# 09_FPGA_E.net
KiCad netlist of a schematic drawn in Altium Designer
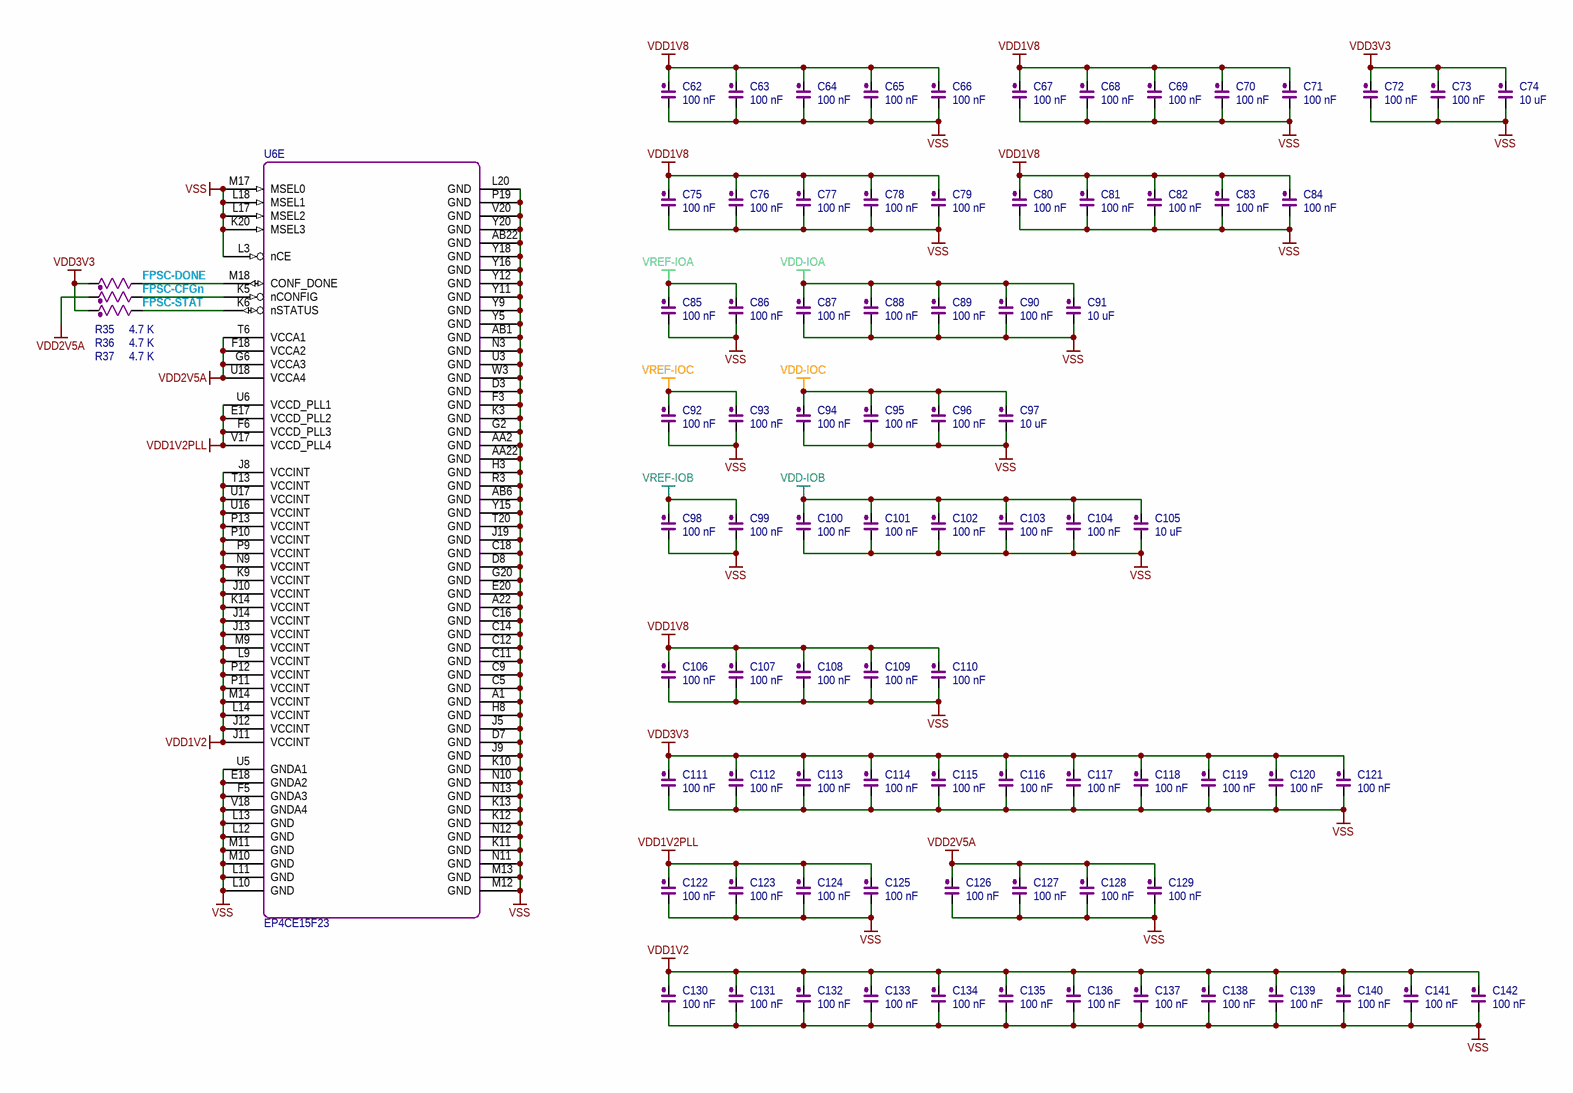
[diagram p0: 09_FPGA_E.SchDoc]

(export (version "E")
  (design (tool "Eeschema 10.0.6"))
  (components
    (comp (ref "C62")
      (value "100 nF")
      (footprint "0402A1")
      (description "Normal Capacitor")
      (fields
        (field (name "PARTNUMBER") "0")
        (field (name "PUBLISHER") "Cowin")
        (field (name "DESIGNER") "shyul")
      )
      (libsource (lib "Basc_1_Passive") (part "CAP"))
    )
    (comp (ref "C63")
      (value "100 nF")
      (footprint "0402A1")
      (description "Normal Capacitor")
      (fields
        (field (name "PARTNUMBER") "0")
        (field (name "PUBLISHER") "Cowin")
        (field (name "DESIGNER") "shyul")
      )
      (libsource (lib "Basc_1_Passive") (part "CAP"))
    )
    (comp (ref "C64")
      (value "100 nF")
      (footprint "0402A1")
      (description "Normal Capacitor")
      (fields
        (field (name "PARTNUMBER") "0")
        (field (name "PUBLISHER") "Cowin")
        (field (name "DESIGNER") "shyul")
      )
      (libsource (lib "Basc_1_Passive") (part "CAP"))
    )
    (comp (ref "C65")
      (value "100 nF")
      (footprint "0402A1")
      (description "Normal Capacitor")
      (fields
        (field (name "PARTNUMBER") "0")
        (field (name "PUBLISHER") "Cowin")
        (field (name "DESIGNER") "shyul")
      )
      (libsource (lib "Basc_1_Passive") (part "CAP"))
    )
    (comp (ref "C66")
      (value "100 nF")
      (footprint "0402A1")
      (description "Normal Capacitor")
      (fields
        (field (name "PARTNUMBER") "0")
        (field (name "PUBLISHER") "Cowin")
        (field (name "DESIGNER") "shyul")
      )
      (libsource (lib "Basc_1_Passive") (part "CAP"))
    )
    (comp (ref "C67")
      (value "100 nF")
      (footprint "0402A1")
      (description "Normal Capacitor")
      (fields
        (field (name "PARTNUMBER") "0")
        (field (name "PUBLISHER") "Cowin")
        (field (name "DESIGNER") "shyul")
      )
      (libsource (lib "Basc_1_Passive") (part "CAP"))
    )
    (comp (ref "C68")
      (value "100 nF")
      (footprint "0402A1")
      (description "Normal Capacitor")
      (fields
        (field (name "PARTNUMBER") "0")
        (field (name "PUBLISHER") "Cowin")
        (field (name "DESIGNER") "shyul")
      )
      (libsource (lib "Basc_1_Passive") (part "CAP"))
    )
    (comp (ref "C69")
      (value "100 nF")
      (footprint "0402A1")
      (description "Normal Capacitor")
      (fields
        (field (name "PARTNUMBER") "0")
        (field (name "PUBLISHER") "Cowin")
        (field (name "DESIGNER") "shyul")
      )
      (libsource (lib "Basc_1_Passive") (part "CAP"))
    )
    (comp (ref "C70")
      (value "100 nF")
      (footprint "0402A1")
      (description "Normal Capacitor")
      (fields
        (field (name "PARTNUMBER") "0")
        (field (name "PUBLISHER") "Cowin")
        (field (name "DESIGNER") "shyul")
      )
      (libsource (lib "Basc_1_Passive") (part "CAP"))
    )
    (comp (ref "C71")
      (value "100 nF")
      (footprint "0402A1")
      (description "Normal Capacitor")
      (fields
        (field (name "PARTNUMBER") "0")
        (field (name "PUBLISHER") "Cowin")
        (field (name "DESIGNER") "shyul")
      )
      (libsource (lib "Basc_1_Passive") (part "CAP"))
    )
    (comp (ref "C72")
      (value "100 nF")
      (footprint "0402A1")
      (description "Normal Capacitor")
      (fields
        (field (name "PARTNUMBER") "0")
        (field (name "PUBLISHER") "Cowin")
        (field (name "DESIGNER") "shyul")
      )
      (libsource (lib "Basc_1_Passive") (part "CAP"))
    )
    (comp (ref "C73")
      (value "100 nF")
      (footprint "0402A1")
      (description "Normal Capacitor")
      (fields
        (field (name "PARTNUMBER") "0")
        (field (name "PUBLISHER") "Cowin")
        (field (name "DESIGNER") "shyul")
      )
      (libsource (lib "Basc_1_Passive") (part "CAP"))
    )
    (comp (ref "C74")
      (value "10 uF")
      (footprint "0603A1")
      (description "Normal Capacitor")
      (fields
        (field (name "PARTNUMBER") "0")
        (field (name "PUBLISHER") "Cowin")
        (field (name "DESIGNER") "shyul")
      )
      (libsource (lib "Basc_1_Passive") (part "CAP"))
    )
    (comp (ref "C75")
      (value "100 nF")
      (footprint "0402A1")
      (description "Normal Capacitor")
      (fields
        (field (name "PARTNUMBER") "0")
        (field (name "PUBLISHER") "Cowin")
        (field (name "DESIGNER") "shyul")
      )
      (libsource (lib "Basc_1_Passive") (part "CAP"))
    )
    (comp (ref "C76")
      (value "100 nF")
      (footprint "0402A1")
      (description "Normal Capacitor")
      (fields
        (field (name "PARTNUMBER") "0")
        (field (name "PUBLISHER") "Cowin")
        (field (name "DESIGNER") "shyul")
      )
      (libsource (lib "Basc_1_Passive") (part "CAP"))
    )
    (comp (ref "C77")
      (value "100 nF")
      (footprint "0402A1")
      (description "Normal Capacitor")
      (fields
        (field (name "PARTNUMBER") "0")
        (field (name "PUBLISHER") "Cowin")
        (field (name "DESIGNER") "shyul")
      )
      (libsource (lib "Basc_1_Passive") (part "CAP"))
    )
    (comp (ref "C78")
      (value "100 nF")
      (footprint "0402A1")
      (description "Normal Capacitor")
      (fields
        (field (name "PARTNUMBER") "0")
        (field (name "PUBLISHER") "Cowin")
        (field (name "DESIGNER") "shyul")
      )
      (libsource (lib "Basc_1_Passive") (part "CAP"))
    )
    (comp (ref "C79")
      (value "100 nF")
      (footprint "0402A1")
      (description "Normal Capacitor")
      (fields
        (field (name "PARTNUMBER") "0")
        (field (name "PUBLISHER") "Cowin")
        (field (name "DESIGNER") "shyul")
      )
      (libsource (lib "Basc_1_Passive") (part "CAP"))
    )
    (comp (ref "C80")
      (value "100 nF")
      (footprint "0402A1")
      (description "Normal Capacitor")
      (fields
        (field (name "PARTNUMBER") "0")
        (field (name "PUBLISHER") "Cowin")
        (field (name "DESIGNER") "shyul")
      )
      (libsource (lib "Basc_1_Passive") (part "CAP"))
    )
    (comp (ref "C81")
      (value "100 nF")
      (footprint "0402A1")
      (description "Normal Capacitor")
      (fields
        (field (name "PARTNUMBER") "0")
        (field (name "PUBLISHER") "Cowin")
        (field (name "DESIGNER") "shyul")
      )
      (libsource (lib "Basc_1_Passive") (part "CAP"))
    )
    (comp (ref "C82")
      (value "100 nF")
      (footprint "0402A1")
      (description "Normal Capacitor")
      (fields
        (field (name "PARTNUMBER") "0")
        (field (name "PUBLISHER") "Cowin")
        (field (name "DESIGNER") "shyul")
      )
      (libsource (lib "Basc_1_Passive") (part "CAP"))
    )
    (comp (ref "C83")
      (value "100 nF")
      (footprint "0402A1")
      (description "Normal Capacitor")
      (fields
        (field (name "PARTNUMBER") "0")
        (field (name "PUBLISHER") "Cowin")
        (field (name "DESIGNER") "shyul")
      )
      (libsource (lib "Basc_1_Passive") (part "CAP"))
    )
    (comp (ref "C84")
      (value "100 nF")
      (footprint "0402A1")
      (description "Normal Capacitor")
      (fields
        (field (name "PARTNUMBER") "0")
        (field (name "PUBLISHER") "Cowin")
        (field (name "DESIGNER") "shyul")
      )
      (libsource (lib "Basc_1_Passive") (part "CAP"))
    )
    (comp (ref "C85")
      (value "100 nF")
      (footprint "0402A1")
      (description "Normal Capacitor")
      (fields
        (field (name "PARTNUMBER") "0")
        (field (name "PUBLISHER") "Cowin")
        (field (name "DESIGNER") "shyul")
      )
      (libsource (lib "Basc_1_Passive") (part "CAP"))
    )
    (comp (ref "C86")
      (value "100 nF")
      (footprint "0402A1")
      (description "Normal Capacitor")
      (fields
        (field (name "PARTNUMBER") "0")
        (field (name "PUBLISHER") "Cowin")
        (field (name "DESIGNER") "shyul")
      )
      (libsource (lib "Basc_1_Passive") (part "CAP"))
    )
    (comp (ref "C87")
      (value "100 nF")
      (footprint "0402A1")
      (description "Normal Capacitor")
      (fields
        (field (name "PARTNUMBER") "0")
        (field (name "PUBLISHER") "Cowin")
        (field (name "DESIGNER") "shyul")
      )
      (libsource (lib "Basc_1_Passive") (part "CAP"))
    )
    (comp (ref "C88")
      (value "100 nF")
      (footprint "0402A1")
      (description "Normal Capacitor")
      (fields
        (field (name "PARTNUMBER") "0")
        (field (name "PUBLISHER") "Cowin")
        (field (name "DESIGNER") "shyul")
      )
      (libsource (lib "Basc_1_Passive") (part "CAP"))
    )
    (comp (ref "C89")
      (value "100 nF")
      (footprint "0402A1")
      (description "Normal Capacitor")
      (fields
        (field (name "PARTNUMBER") "0")
        (field (name "PUBLISHER") "Cowin")
        (field (name "DESIGNER") "shyul")
      )
      (libsource (lib "Basc_1_Passive") (part "CAP"))
    )
    (comp (ref "C90")
      (value "100 nF")
      (footprint "0402A1")
      (description "Normal Capacitor")
      (fields
        (field (name "PARTNUMBER") "0")
        (field (name "PUBLISHER") "Cowin")
        (field (name "DESIGNER") "shyul")
      )
      (libsource (lib "Basc_1_Passive") (part "CAP"))
    )
    (comp (ref "C91")
      (value "10 uF")
      (footprint "0603A1")
      (description "Normal Capacitor")
      (fields
        (field (name "PARTNUMBER") "0")
        (field (name "PUBLISHER") "Cowin")
        (field (name "DESIGNER") "shyul")
      )
      (libsource (lib "Basc_1_Passive") (part "CAP"))
    )
    (comp (ref "C92")
      (value "100 nF")
      (footprint "0402A1")
      (description "Normal Capacitor")
      (fields
        (field (name "PARTNUMBER") "0")
        (field (name "PUBLISHER") "Cowin")
        (field (name "DESIGNER") "shyul")
      )
      (libsource (lib "Basc_1_Passive") (part "CAP"))
    )
    (comp (ref "C93")
      (value "100 nF")
      (footprint "0402A1")
      (description "Normal Capacitor")
      (fields
        (field (name "PARTNUMBER") "0")
        (field (name "PUBLISHER") "Cowin")
        (field (name "DESIGNER") "shyul")
      )
      (libsource (lib "Basc_1_Passive") (part "CAP"))
    )
    (comp (ref "C94")
      (value "100 nF")
      (footprint "0402A1")
      (description "Normal Capacitor")
      (fields
        (field (name "PARTNUMBER") "0")
        (field (name "PUBLISHER") "Cowin")
        (field (name "DESIGNER") "shyul")
      )
      (libsource (lib "Basc_1_Passive") (part "CAP"))
    )
    (comp (ref "C95")
      (value "100 nF")
      (footprint "0402A1")
      (description "Normal Capacitor")
      (fields
        (field (name "PARTNUMBER") "0")
        (field (name "PUBLISHER") "Cowin")
        (field (name "DESIGNER") "shyul")
      )
      (libsource (lib "Basc_1_Passive") (part "CAP"))
    )
    (comp (ref "C96")
      (value "100 nF")
      (footprint "0402A1")
      (description "Normal Capacitor")
      (fields
        (field (name "PARTNUMBER") "0")
        (field (name "PUBLISHER") "Cowin")
        (field (name "DESIGNER") "shyul")
      )
      (libsource (lib "Basc_1_Passive") (part "CAP"))
    )
    (comp (ref "C97")
      (value "10 uF")
      (footprint "0603A1")
      (description "Normal Capacitor")
      (fields
        (field (name "PARTNUMBER") "0")
        (field (name "PUBLISHER") "Cowin")
        (field (name "DESIGNER") "shyul")
      )
      (libsource (lib "Basc_1_Passive") (part "CAP"))
    )
    (comp (ref "C98")
      (value "100 nF")
      (footprint "0402A1")
      (description "Normal Capacitor")
      (fields
        (field (name "PARTNUMBER") "0")
        (field (name "PUBLISHER") "Cowin")
        (field (name "DESIGNER") "shyul")
      )
      (libsource (lib "Basc_1_Passive") (part "CAP"))
    )
    (comp (ref "C99")
      (value "100 nF")
      (footprint "0402A1")
      (description "Normal Capacitor")
      (fields
        (field (name "PARTNUMBER") "0")
        (field (name "PUBLISHER") "Cowin")
        (field (name "DESIGNER") "shyul")
      )
      (libsource (lib "Basc_1_Passive") (part "CAP"))
    )
    (comp (ref "C100")
      (value "100 nF")
      (footprint "0402A1")
      (description "Normal Capacitor")
      (fields
        (field (name "PARTNUMBER") "0")
        (field (name "PUBLISHER") "Cowin")
        (field (name "DESIGNER") "shyul")
      )
      (libsource (lib "Basc_1_Passive") (part "CAP"))
    )
    (comp (ref "C101")
      (value "100 nF")
      (footprint "0402A1")
      (description "Normal Capacitor")
      (fields
        (field (name "PARTNUMBER") "0")
        (field (name "PUBLISHER") "Cowin")
        (field (name "DESIGNER") "shyul")
      )
      (libsource (lib "Basc_1_Passive") (part "CAP"))
    )
    (comp (ref "C102")
      (value "100 nF")
      (footprint "0402A1")
      (description "Normal Capacitor")
      (fields
        (field (name "PARTNUMBER") "0")
        (field (name "PUBLISHER") "Cowin")
        (field (name "DESIGNER") "shyul")
      )
      (libsource (lib "Basc_1_Passive") (part "CAP"))
    )
    (comp (ref "C103")
      (value "100 nF")
      (footprint "0402BG")
      (description "Normal Capacitor")
      (fields
        (field (name "PARTNUMBER") "0")
        (field (name "PUBLISHER") "Cowin")
        (field (name "DESIGNER") "shyul")
      )
      (libsource (lib "Basc_1_Passive") (part "CAP"))
    )
    (comp (ref "C104")
      (value "100 nF")
      (footprint "0402BG")
      (description "Normal Capacitor")
      (fields
        (field (name "PARTNUMBER") "0")
        (field (name "PUBLISHER") "Cowin")
        (field (name "DESIGNER") "shyul")
      )
      (libsource (lib "Basc_1_Passive") (part "CAP"))
    )
    (comp (ref "C105")
      (value "10 uF")
      (footprint "0603A1")
      (description "Normal Capacitor")
      (fields
        (field (name "PARTNUMBER") "0")
        (field (name "PUBLISHER") "Cowin")
        (field (name "DESIGNER") "shyul")
      )
      (libsource (lib "Basc_1_Passive") (part "CAP"))
    )
    (comp (ref "C106")
      (value "100 nF")
      (footprint "0402BG")
      (description "Normal Capacitor")
      (fields
        (field (name "PARTNUMBER") "0")
        (field (name "PUBLISHER") "Cowin")
        (field (name "DESIGNER") "shyul")
      )
      (libsource (lib "Basc_1_Passive") (part "CAP"))
    )
    (comp (ref "C107")
      (value "100 nF")
      (footprint "0402BG")
      (description "Normal Capacitor")
      (fields
        (field (name "PARTNUMBER") "0")
        (field (name "PUBLISHER") "Cowin")
        (field (name "DESIGNER") "shyul")
      )
      (libsource (lib "Basc_1_Passive") (part "CAP"))
    )
    (comp (ref "C108")
      (value "100 nF")
      (footprint "0402BG")
      (description "Normal Capacitor")
      (fields
        (field (name "PARTNUMBER") "0")
        (field (name "PUBLISHER") "Cowin")
        (field (name "DESIGNER") "shyul")
      )
      (libsource (lib "Basc_1_Passive") (part "CAP"))
    )
    (comp (ref "C109")
      (value "100 nF")
      (footprint "0402BG")
      (description "Normal Capacitor")
      (fields
        (field (name "PARTNUMBER") "0")
        (field (name "PUBLISHER") "Cowin")
        (field (name "DESIGNER") "shyul")
      )
      (libsource (lib "Basc_1_Passive") (part "CAP"))
    )
    (comp (ref "C110")
      (value "100 nF")
      (footprint "0402BG")
      (description "Normal Capacitor")
      (fields
        (field (name "PARTNUMBER") "0")
        (field (name "PUBLISHER") "Cowin")
        (field (name "DESIGNER") "shyul")
      )
      (libsource (lib "Basc_1_Passive") (part "CAP"))
    )
    (comp (ref "C111")
      (value "100 nF")
      (footprint "0402BG")
      (description "Normal Capacitor")
      (fields
        (field (name "PARTNUMBER") "0")
        (field (name "PUBLISHER") "Cowin")
        (field (name "DESIGNER") "shyul")
      )
      (libsource (lib "Basc_1_Passive") (part "CAP"))
    )
    (comp (ref "C112")
      (value "100 nF")
      (footprint "0402BG")
      (description "Normal Capacitor")
      (fields
        (field (name "PARTNUMBER") "0")
        (field (name "PUBLISHER") "Cowin")
        (field (name "DESIGNER") "shyul")
      )
      (libsource (lib "Basc_1_Passive") (part "CAP"))
    )
    (comp (ref "C113")
      (value "100 nF")
      (footprint "0402BG")
      (description "Normal Capacitor")
      (fields
        (field (name "PARTNUMBER") "0")
        (field (name "PUBLISHER") "Cowin")
        (field (name "DESIGNER") "shyul")
      )
      (libsource (lib "Basc_1_Passive") (part "CAP"))
    )
    (comp (ref "C114")
      (value "100 nF")
      (footprint "0402BG")
      (description "Normal Capacitor")
      (fields
        (field (name "PARTNUMBER") "0")
        (field (name "PUBLISHER") "Cowin")
        (field (name "DESIGNER") "shyul")
      )
      (libsource (lib "Basc_1_Passive") (part "CAP"))
    )
    (comp (ref "C115")
      (value "100 nF")
      (footprint "0402BG")
      (description "Normal Capacitor")
      (fields
        (field (name "PARTNUMBER") "0")
        (field (name "PUBLISHER") "Cowin")
        (field (name "DESIGNER") "shyul")
      )
      (libsource (lib "Basc_1_Passive") (part "CAP"))
    )
    (comp (ref "C116")
      (value "100 nF")
      (footprint "0402BG")
      (description "Normal Capacitor")
      (fields
        (field (name "PARTNUMBER") "0")
        (field (name "PUBLISHER") "Cowin")
        (field (name "DESIGNER") "shyul")
      )
      (libsource (lib "Basc_1_Passive") (part "CAP"))
    )
    (comp (ref "C117")
      (value "100 nF")
      (footprint "0402BG")
      (description "Normal Capacitor")
      (fields
        (field (name "PARTNUMBER") "0")
        (field (name "PUBLISHER") "Cowin")
        (field (name "DESIGNER") "shyul")
      )
      (libsource (lib "Basc_1_Passive") (part "CAP"))
    )
    (comp (ref "C118")
      (value "100 nF")
      (footprint "0402BG")
      (description "Normal Capacitor")
      (fields
        (field (name "PARTNUMBER") "0")
        (field (name "PUBLISHER") "Cowin")
        (field (name "DESIGNER") "shyul")
      )
      (libsource (lib "Basc_1_Passive") (part "CAP"))
    )
    (comp (ref "C119")
      (value "100 nF")
      (footprint "0402BG")
      (description "Normal Capacitor")
      (fields
        (field (name "PARTNUMBER") "0")
        (field (name "PUBLISHER") "Cowin")
        (field (name "DESIGNER") "shyul")
      )
      (libsource (lib "Basc_1_Passive") (part "CAP"))
    )
    (comp (ref "C120")
      (value "100 nF")
      (footprint "0402BG")
      (description "Normal Capacitor")
      (fields
        (field (name "PARTNUMBER") "0")
        (field (name "PUBLISHER") "Cowin")
        (field (name "DESIGNER") "shyul")
      )
      (libsource (lib "Basc_1_Passive") (part "CAP"))
    )
    (comp (ref "C121")
      (value "100 nF")
      (footprint "0402BG")
      (description "Normal Capacitor")
      (fields
        (field (name "PARTNUMBER") "0")
        (field (name "PUBLISHER") "Cowin")
        (field (name "DESIGNER") "shyul")
      )
      (libsource (lib "Basc_1_Passive") (part "CAP"))
    )
    (comp (ref "C122")
      (value "100 nF")
      (footprint "0402BG")
      (description "Normal Capacitor")
      (fields
        (field (name "PARTNUMBER") "0")
        (field (name "PUBLISHER") "Cowin")
        (field (name "DESIGNER") "shyul")
      )
      (libsource (lib "Basc_1_Passive") (part "CAP"))
    )
    (comp (ref "C123")
      (value "100 nF")
      (footprint "0402BG")
      (description "Normal Capacitor")
      (fields
        (field (name "PARTNUMBER") "0")
        (field (name "PUBLISHER") "Cowin")
        (field (name "DESIGNER") "shyul")
      )
      (libsource (lib "Basc_1_Passive") (part "CAP"))
    )
    (comp (ref "C124")
      (value "100 nF")
      (footprint "0402BG")
      (description "Normal Capacitor")
      (fields
        (field (name "PARTNUMBER") "0")
        (field (name "PUBLISHER") "Cowin")
        (field (name "DESIGNER") "shyul")
      )
      (libsource (lib "Basc_1_Passive") (part "CAP"))
    )
    (comp (ref "C125")
      (value "100 nF")
      (footprint "0402BG")
      (description "Normal Capacitor")
      (fields
        (field (name "PARTNUMBER") "0")
        (field (name "PUBLISHER") "Cowin")
        (field (name "DESIGNER") "shyul")
      )
      (libsource (lib "Basc_1_Passive") (part "CAP"))
    )
    (comp (ref "C126")
      (value "100 nF")
      (footprint "0402BG")
      (description "Normal Capacitor")
      (fields
        (field (name "PARTNUMBER") "0")
        (field (name "PUBLISHER") "Cowin")
        (field (name "DESIGNER") "shyul")
      )
      (libsource (lib "Basc_1_Passive") (part "CAP"))
    )
    (comp (ref "C127")
      (value "100 nF")
      (footprint "0402BG")
      (description "Normal Capacitor")
      (fields
        (field (name "PARTNUMBER") "0")
        (field (name "PUBLISHER") "Cowin")
        (field (name "DESIGNER") "shyul")
      )
      (libsource (lib "Basc_1_Passive") (part "CAP"))
    )
    (comp (ref "C128")
      (value "100 nF")
      (footprint "0402BG")
      (description "Normal Capacitor")
      (fields
        (field (name "PARTNUMBER") "0")
        (field (name "PUBLISHER") "Cowin")
        (field (name "DESIGNER") "shyul")
      )
      (libsource (lib "Basc_1_Passive") (part "CAP"))
    )
    (comp (ref "C129")
      (value "100 nF")
      (footprint "0402BG")
      (description "Normal Capacitor")
      (fields
        (field (name "PARTNUMBER") "0")
        (field (name "PUBLISHER") "Cowin")
        (field (name "DESIGNER") "shyul")
      )
      (libsource (lib "Basc_1_Passive") (part "CAP"))
    )
    (comp (ref "C130")
      (value "100 nF")
      (footprint "0402BG")
      (description "Normal Capacitor")
      (fields
        (field (name "PARTNUMBER") "0")
        (field (name "PUBLISHER") "Cowin")
        (field (name "DESIGNER") "shyul")
      )
      (libsource (lib "Basc_1_Passive") (part "CAP"))
    )
    (comp (ref "C131")
      (value "100 nF")
      (footprint "0402BG")
      (description "Normal Capacitor")
      (fields
        (field (name "PARTNUMBER") "0")
        (field (name "PUBLISHER") "Cowin")
        (field (name "DESIGNER") "shyul")
      )
      (libsource (lib "Basc_1_Passive") (part "CAP"))
    )
    (comp (ref "C132")
      (value "100 nF")
      (footprint "0402BG")
      (description "Normal Capacitor")
      (fields
        (field (name "PARTNUMBER") "0")
        (field (name "PUBLISHER") "Cowin")
        (field (name "DESIGNER") "shyul")
      )
      (libsource (lib "Basc_1_Passive") (part "CAP"))
    )
    (comp (ref "C133")
      (value "100 nF")
      (footprint "0402BG")
      (description "Normal Capacitor")
      (fields
        (field (name "PARTNUMBER") "0")
        (field (name "PUBLISHER") "Cowin")
        (field (name "DESIGNER") "shyul")
      )
      (libsource (lib "Basc_1_Passive") (part "CAP"))
    )
    (comp (ref "C134")
      (value "100 nF")
      (footprint "0402BG")
      (description "Normal Capacitor")
      (fields
        (field (name "PARTNUMBER") "0")
        (field (name "PUBLISHER") "Cowin")
        (field (name "DESIGNER") "shyul")
      )
      (libsource (lib "Basc_1_Passive") (part "CAP"))
    )
    (comp (ref "C135")
      (value "100 nF")
      (footprint "0402BG")
      (description "Normal Capacitor")
      (fields
        (field (name "PARTNUMBER") "0")
        (field (name "PUBLISHER") "Cowin")
        (field (name "DESIGNER") "shyul")
      )
      (libsource (lib "Basc_1_Passive") (part "CAP"))
    )
    (comp (ref "C136")
      (value "100 nF")
      (footprint "0402BG")
      (description "Normal Capacitor")
      (fields
        (field (name "PARTNUMBER") "0")
        (field (name "PUBLISHER") "Cowin")
        (field (name "DESIGNER") "shyul")
      )
      (libsource (lib "Basc_1_Passive") (part "CAP"))
    )
    (comp (ref "C137")
      (value "100 nF")
      (footprint "0402BG")
      (description "Normal Capacitor")
      (fields
        (field (name "PARTNUMBER") "0")
        (field (name "PUBLISHER") "Cowin")
        (field (name "DESIGNER") "shyul")
      )
      (libsource (lib "Basc_1_Passive") (part "CAP"))
    )
    (comp (ref "C138")
      (value "100 nF")
      (footprint "0402BG")
      (description "Normal Capacitor")
      (fields
        (field (name "PARTNUMBER") "0")
        (field (name "PUBLISHER") "Cowin")
        (field (name "DESIGNER") "shyul")
      )
      (libsource (lib "Basc_1_Passive") (part "CAP"))
    )
    (comp (ref "C139")
      (value "100 nF")
      (footprint "0402BG")
      (description "Normal Capacitor")
      (fields
        (field (name "PARTNUMBER") "0")
        (field (name "PUBLISHER") "Cowin")
        (field (name "DESIGNER") "shyul")
      )
      (libsource (lib "Basc_1_Passive") (part "CAP"))
    )
    (comp (ref "C140")
      (value "100 nF")
      (footprint "0402BG")
      (description "Normal Capacitor")
      (fields
        (field (name "PARTNUMBER") "0")
        (field (name "PUBLISHER") "Cowin")
        (field (name "DESIGNER") "shyul")
      )
      (libsource (lib "Basc_1_Passive") (part "CAP"))
    )
    (comp (ref "C141")
      (value "100 nF")
      (footprint "0402BG")
      (description "Normal Capacitor")
      (fields
        (field (name "PARTNUMBER") "0")
        (field (name "PUBLISHER") "Cowin")
        (field (name "DESIGNER") "shyul")
      )
      (libsource (lib "Basc_1_Passive") (part "CAP"))
    )
    (comp (ref "C142")
      (value "100 nF")
      (footprint "0402BG")
      (description "Normal Capacitor")
      (fields
        (field (name "PARTNUMBER") "0")
        (field (name "PUBLISHER") "Cowin")
        (field (name "DESIGNER") "shyul")
      )
      (libsource (lib "Basc_1_Passive") (part "CAP"))
    )
    (comp (ref "R35")
      (value "4.7 K")
      (footprint "0402A2")
      (description "Normal Resistor")
      (fields
        (field (name "PARTNUMBER") "0")
        (field (name "DESIGNER") "shyul")
        (field (name "PUBLISHER") "Cowin")
      )
      (libsource (lib "Basc_1_Passive") (part "RES"))
    )
    (comp (ref "R36")
      (value "4.7 K")
      (footprint "0402A2")
      (description "Normal Resistor")
      (fields
        (field (name "PARTNUMBER") "0")
        (field (name "DESIGNER") "shyul")
        (field (name "PUBLISHER") "Cowin")
      )
      (libsource (lib "Basc_1_Passive") (part "RES"))
    )
    (comp (ref "R37")
      (value "4.7 K")
      (footprint "0402A2")
      (description "Normal Resistor")
      (fields
        (field (name "PARTNUMBER") "0")
        (field (name "DESIGNER") "shyul")
        (field (name "PUBLISHER") "Cowin")
      )
      (libsource (lib "Basc_1_Passive") (part "RES"))
    )
    (comp (ref "U6")
      (value "EP4CE15F23")
      (footprint "FBGA-484")
      (description "Cyclone IV EP4CE15F23 FPGA")
      (fields
        (field (name "PARTNUMBER") "EP4CE15F23C8N")
        (field (name "DESIGNER") "shyul")
        (field (name "PUBLISHER") "Cowin")
      )
      (libsource (lib "PCB_XEM-S91") (part "EP4CE15F23"))
    )
  )
  (nets
    (net (code "1") (name "/FPSC-CFGn") (class "Default")
      (node (ref "R36") (pin "1") (pinfunction "1_1") (pintype "passive"))
      (node (ref "U6") (pin "K5") (pinfunction "nCONFIG_K5") (pintype "input"))
    )
    (net (code "2") (name "/FPSC-DONE") (class "Default")
      (node (ref "R35") (pin "1") (pinfunction "1_1") (pintype "passive"))
      (node (ref "U6") (pin "M18") (pinfunction "CONF_DONE_M18") (pintype "bidirectional"))
    )
    (net (code "3") (name "/FPSC-STAT") (class "Default")
      (node (ref "R37") (pin "1") (pinfunction "1_1") (pintype "passive"))
      (node (ref "U6") (pin "K6") (pinfunction "nSTATUS_K6") (pintype "bidirectional"))
    )
    (net (code "4") (name "VDD-IOA") (class "Default")
      (node (ref "C87") (pin "2") (pinfunction "2_2") (pintype "passive"))
      (node (ref "C88") (pin "2") (pinfunction "2_2") (pintype "passive"))
      (node (ref "C89") (pin "2") (pinfunction "2_2") (pintype "passive"))
      (node (ref "C90") (pin "2") (pinfunction "2_2") (pintype "passive"))
      (node (ref "C91") (pin "2") (pinfunction "2_2") (pintype "passive"))
    )
    (net (code "5") (name "VDD-IOB") (class "Default")
      (node (ref "C100") (pin "2") (pinfunction "2_2") (pintype "passive"))
      (node (ref "C101") (pin "2") (pinfunction "2_2") (pintype "passive"))
      (node (ref "C102") (pin "2") (pinfunction "2_2") (pintype "passive"))
      (node (ref "C103") (pin "2") (pinfunction "2_2") (pintype "passive"))
      (node (ref "C104") (pin "2") (pinfunction "2_2") (pintype "passive"))
      (node (ref "C105") (pin "2") (pinfunction "2_2") (pintype "passive"))
    )
    (net (code "6") (name "VDD-IOC") (class "Default")
      (node (ref "C94") (pin "2") (pinfunction "2_2") (pintype "passive"))
      (node (ref "C95") (pin "2") (pinfunction "2_2") (pintype "passive"))
      (node (ref "C96") (pin "2") (pinfunction "2_2") (pintype "passive"))
      (node (ref "C97") (pin "2") (pinfunction "2_2") (pintype "passive"))
    )
    (net (code "7") (name "VDD1V2") (class "Default")
      (node (ref "C130") (pin "2") (pinfunction "2_2") (pintype "passive"))
      (node (ref "C131") (pin "2") (pinfunction "2_2") (pintype "passive"))
      (node (ref "C132") (pin "2") (pinfunction "2_2") (pintype "passive"))
      (node (ref "C133") (pin "2") (pinfunction "2_2") (pintype "passive"))
      (node (ref "C134") (pin "2") (pinfunction "2_2") (pintype "passive"))
      (node (ref "C135") (pin "2") (pinfunction "2_2") (pintype "passive"))
      (node (ref "C136") (pin "2") (pinfunction "2_2") (pintype "passive"))
      (node (ref "C137") (pin "2") (pinfunction "2_2") (pintype "passive"))
      (node (ref "C138") (pin "2") (pinfunction "2_2") (pintype "passive"))
      (node (ref "C139") (pin "2") (pinfunction "2_2") (pintype "passive"))
      (node (ref "C140") (pin "2") (pinfunction "2_2") (pintype "passive"))
      (node (ref "C141") (pin "2") (pinfunction "2_2") (pintype "passive"))
      (node (ref "C142") (pin "2") (pinfunction "2_2") (pintype "passive"))
      (node (ref "U6") (pin "J10") (pinfunction "VCCINT_J10") (pintype "power_in"))
      (node (ref "U6") (pin "J11") (pinfunction "VCCINT_J11") (pintype "power_in"))
      (node (ref "U6") (pin "J12") (pinfunction "VCCINT_J12") (pintype "power_in"))
      (node (ref "U6") (pin "J13") (pinfunction "VCCINT_J13") (pintype "power_in"))
      (node (ref "U6") (pin "J14") (pinfunction "VCCINT_J14") (pintype "power_in"))
      (node (ref "U6") (pin "J8") (pinfunction "VCCINT_J8") (pintype "power_in"))
      (node (ref "U6") (pin "K14") (pinfunction "VCCINT_K14") (pintype "power_in"))
      (node (ref "U6") (pin "K9") (pinfunction "VCCINT_K9") (pintype "power_in"))
      (node (ref "U6") (pin "L14") (pinfunction "VCCINT_L14") (pintype "power_in"))
      (node (ref "U6") (pin "L9") (pinfunction "VCCINT_L9") (pintype "power_in"))
      (node (ref "U6") (pin "M14") (pinfunction "VCCINT_M14") (pintype "power_in"))
      (node (ref "U6") (pin "M9") (pinfunction "VCCINT_M9") (pintype "power_in"))
      (node (ref "U6") (pin "N9") (pinfunction "VCCINT_N9") (pintype "power_in"))
      (node (ref "U6") (pin "P10") (pinfunction "VCCINT_P10") (pintype "power_in"))
      (node (ref "U6") (pin "P11") (pinfunction "VCCINT_P11") (pintype "power_in"))
      (node (ref "U6") (pin "P12") (pinfunction "VCCINT_P12") (pintype "power_in"))
      (node (ref "U6") (pin "P13") (pinfunction "VCCINT_P13") (pintype "power_in"))
      (node (ref "U6") (pin "P9") (pinfunction "VCCINT_P9") (pintype "power_in"))
      (node (ref "U6") (pin "T13") (pinfunction "VCCINT_T13") (pintype "power_in"))
      (node (ref "U6") (pin "U16") (pinfunction "VCCINT_U16") (pintype "power_in"))
      (node (ref "U6") (pin "U17") (pinfunction "VCCINT_U17") (pintype "power_in"))
    )
    (net (code "8") (name "VDD1V2PLL") (class "Default")
      (node (ref "C122") (pin "2") (pinfunction "2_2") (pintype "passive"))
      (node (ref "C123") (pin "2") (pinfunction "2_2") (pintype "passive"))
      (node (ref "C124") (pin "2") (pinfunction "2_2") (pintype "passive"))
      (node (ref "C125") (pin "2") (pinfunction "2_2") (pintype "passive"))
      (node (ref "U6") (pin "E17") (pinfunction "VCCD_PLL2_E17") (pintype "power_in"))
      (node (ref "U6") (pin "F6") (pinfunction "VCCD_PLL3_F6") (pintype "power_in"))
      (node (ref "U6") (pin "U6") (pinfunction "VCCD_PLL1_U6") (pintype "power_in"))
      (node (ref "U6") (pin "V17") (pinfunction "VCCD_PLL4_V17") (pintype "power_in"))
    )
    (net (code "9") (name "VDD1V8") (class "Default")
      (node (ref "C106") (pin "2") (pinfunction "2_2") (pintype "passive"))
      (node (ref "C107") (pin "2") (pinfunction "2_2") (pintype "passive"))
      (node (ref "C108") (pin "2") (pinfunction "2_2") (pintype "passive"))
      (node (ref "C109") (pin "2") (pinfunction "2_2") (pintype "passive"))
      (node (ref "C110") (pin "2") (pinfunction "2_2") (pintype "passive"))
      (node (ref "C62") (pin "2") (pinfunction "2_2") (pintype "passive"))
      (node (ref "C63") (pin "2") (pinfunction "2_2") (pintype "passive"))
      (node (ref "C64") (pin "2") (pinfunction "2_2") (pintype "passive"))
      (node (ref "C65") (pin "2") (pinfunction "2_2") (pintype "passive"))
      (node (ref "C66") (pin "2") (pinfunction "2_2") (pintype "passive"))
      (node (ref "C67") (pin "2") (pinfunction "2_2") (pintype "passive"))
      (node (ref "C68") (pin "2") (pinfunction "2_2") (pintype "passive"))
      (node (ref "C69") (pin "2") (pinfunction "2_2") (pintype "passive"))
      (node (ref "C70") (pin "2") (pinfunction "2_2") (pintype "passive"))
      (node (ref "C71") (pin "2") (pinfunction "2_2") (pintype "passive"))
      (node (ref "C75") (pin "2") (pinfunction "2_2") (pintype "passive"))
      (node (ref "C76") (pin "2") (pinfunction "2_2") (pintype "passive"))
      (node (ref "C77") (pin "2") (pinfunction "2_2") (pintype "passive"))
      (node (ref "C78") (pin "2") (pinfunction "2_2") (pintype "passive"))
      (node (ref "C79") (pin "2") (pinfunction "2_2") (pintype "passive"))
      (node (ref "C80") (pin "2") (pinfunction "2_2") (pintype "passive"))
      (node (ref "C81") (pin "2") (pinfunction "2_2") (pintype "passive"))
      (node (ref "C82") (pin "2") (pinfunction "2_2") (pintype "passive"))
      (node (ref "C83") (pin "2") (pinfunction "2_2") (pintype "passive"))
      (node (ref "C84") (pin "2") (pinfunction "2_2") (pintype "passive"))
    )
    (net (code "10") (name "VDD2V5A") (class "Default")
      (node (ref "C126") (pin "2") (pinfunction "2_2") (pintype "passive"))
      (node (ref "C127") (pin "2") (pinfunction "2_2") (pintype "passive"))
      (node (ref "C128") (pin "2") (pinfunction "2_2") (pintype "passive"))
      (node (ref "C129") (pin "2") (pinfunction "2_2") (pintype "passive"))
      (node (ref "R36") (pin "2") (pinfunction "2_2") (pintype "passive"))
      (node (ref "U6") (pin "F18") (pinfunction "VCCA2_F18") (pintype "power_in"))
      (node (ref "U6") (pin "G6") (pinfunction "VCCA3_G6") (pintype "power_in"))
      (node (ref "U6") (pin "T6") (pinfunction "VCCA1_T6") (pintype "power_in"))
      (node (ref "U6") (pin "U18") (pinfunction "VCCA4_U18") (pintype "power_in"))
    )
    (net (code "11") (name "VDD3V3") (class "Default")
      (node (ref "C111") (pin "2") (pinfunction "2_2") (pintype "passive"))
      (node (ref "C112") (pin "2") (pinfunction "2_2") (pintype "passive"))
      (node (ref "C113") (pin "2") (pinfunction "2_2") (pintype "passive"))
      (node (ref "C114") (pin "2") (pinfunction "2_2") (pintype "passive"))
      (node (ref "C115") (pin "2") (pinfunction "2_2") (pintype "passive"))
      (node (ref "C116") (pin "2") (pinfunction "2_2") (pintype "passive"))
      (node (ref "C117") (pin "2") (pinfunction "2_2") (pintype "passive"))
      (node (ref "C118") (pin "2") (pinfunction "2_2") (pintype "passive"))
      (node (ref "C119") (pin "2") (pinfunction "2_2") (pintype "passive"))
      (node (ref "C120") (pin "2") (pinfunction "2_2") (pintype "passive"))
      (node (ref "C121") (pin "2") (pinfunction "2_2") (pintype "passive"))
      (node (ref "C72") (pin "2") (pinfunction "2_2") (pintype "passive"))
      (node (ref "C73") (pin "2") (pinfunction "2_2") (pintype "passive"))
      (node (ref "C74") (pin "2") (pinfunction "2_2") (pintype "passive"))
      (node (ref "R35") (pin "2") (pinfunction "2_2") (pintype "passive"))
      (node (ref "R37") (pin "2") (pinfunction "2_2") (pintype "passive"))
    )
    (net (code "12") (name "VREF-IOA") (class "Default")
      (node (ref "C85") (pin "2") (pinfunction "2_2") (pintype "passive"))
      (node (ref "C86") (pin "2") (pinfunction "2_2") (pintype "passive"))
    )
    (net (code "13") (name "VREF-IOB") (class "Default")
      (node (ref "C98") (pin "2") (pinfunction "2_2") (pintype "passive"))
      (node (ref "C99") (pin "2") (pinfunction "2_2") (pintype "passive"))
    )
    (net (code "14") (name "VREF-IOC") (class "Default")
      (node (ref "C92") (pin "2") (pinfunction "2_2") (pintype "passive"))
      (node (ref "C93") (pin "2") (pinfunction "2_2") (pintype "passive"))
    )
    (net (code "15") (name "VSS") (class "Default")
      (node (ref "C100") (pin "1") (pinfunction "1_1") (pintype "passive"))
      (node (ref "C101") (pin "1") (pinfunction "1_1") (pintype "passive"))
      (node (ref "C102") (pin "1") (pinfunction "1_1") (pintype "passive"))
      (node (ref "C103") (pin "1") (pinfunction "1_1") (pintype "passive"))
      (node (ref "C104") (pin "1") (pinfunction "1_1") (pintype "passive"))
      (node (ref "C105") (pin "1") (pinfunction "1_1") (pintype "passive"))
      (node (ref "C106") (pin "1") (pinfunction "1_1") (pintype "passive"))
      (node (ref "C107") (pin "1") (pinfunction "1_1") (pintype "passive"))
      (node (ref "C108") (pin "1") (pinfunction "1_1") (pintype "passive"))
      (node (ref "C109") (pin "1") (pinfunction "1_1") (pintype "passive"))
      (node (ref "C110") (pin "1") (pinfunction "1_1") (pintype "passive"))
      (node (ref "C111") (pin "1") (pinfunction "1_1") (pintype "passive"))
      (node (ref "C112") (pin "1") (pinfunction "1_1") (pintype "passive"))
      (node (ref "C113") (pin "1") (pinfunction "1_1") (pintype "passive"))
      (node (ref "C114") (pin "1") (pinfunction "1_1") (pintype "passive"))
      (node (ref "C115") (pin "1") (pinfunction "1_1") (pintype "passive"))
      (node (ref "C116") (pin "1") (pinfunction "1_1") (pintype "passive"))
      (node (ref "C117") (pin "1") (pinfunction "1_1") (pintype "passive"))
      (node (ref "C118") (pin "1") (pinfunction "1_1") (pintype "passive"))
      (node (ref "C119") (pin "1") (pinfunction "1_1") (pintype "passive"))
      (node (ref "C120") (pin "1") (pinfunction "1_1") (pintype "passive"))
      (node (ref "C121") (pin "1") (pinfunction "1_1") (pintype "passive"))
      (node (ref "C122") (pin "1") (pinfunction "1_1") (pintype "passive"))
      (node (ref "C123") (pin "1") (pinfunction "1_1") (pintype "passive"))
      (node (ref "C124") (pin "1") (pinfunction "1_1") (pintype "passive"))
      (node (ref "C125") (pin "1") (pinfunction "1_1") (pintype "passive"))
      (node (ref "C126") (pin "1") (pinfunction "1_1") (pintype "passive"))
      (node (ref "C127") (pin "1") (pinfunction "1_1") (pintype "passive"))
      (node (ref "C128") (pin "1") (pinfunction "1_1") (pintype "passive"))
      (node (ref "C129") (pin "1") (pinfunction "1_1") (pintype "passive"))
      (node (ref "C130") (pin "1") (pinfunction "1_1") (pintype "passive"))
      (node (ref "C131") (pin "1") (pinfunction "1_1") (pintype "passive"))
      (node (ref "C132") (pin "1") (pinfunction "1_1") (pintype "passive"))
      (node (ref "C133") (pin "1") (pinfunction "1_1") (pintype "passive"))
      (node (ref "C134") (pin "1") (pinfunction "1_1") (pintype "passive"))
      (node (ref "C135") (pin "1") (pinfunction "1_1") (pintype "passive"))
      (node (ref "C136") (pin "1") (pinfunction "1_1") (pintype "passive"))
      (node (ref "C137") (pin "1") (pinfunction "1_1") (pintype "passive"))
      (node (ref "C138") (pin "1") (pinfunction "1_1") (pintype "passive"))
      (node (ref "C139") (pin "1") (pinfunction "1_1") (pintype "passive"))
      (node (ref "C140") (pin "1") (pinfunction "1_1") (pintype "passive"))
      (node (ref "C141") (pin "1") (pinfunction "1_1") (pintype "passive"))
      (node (ref "C142") (pin "1") (pinfunction "1_1") (pintype "passive"))
      (node (ref "C62") (pin "1") (pinfunction "1_1") (pintype "passive"))
      (node (ref "C63") (pin "1") (pinfunction "1_1") (pintype "passive"))
      (node (ref "C64") (pin "1") (pinfunction "1_1") (pintype "passive"))
      (node (ref "C65") (pin "1") (pinfunction "1_1") (pintype "passive"))
      (node (ref "C66") (pin "1") (pinfunction "1_1") (pintype "passive"))
      (node (ref "C67") (pin "1") (pinfunction "1_1") (pintype "passive"))
      (node (ref "C68") (pin "1") (pinfunction "1_1") (pintype "passive"))
      (node (ref "C69") (pin "1") (pinfunction "1_1") (pintype "passive"))
      (node (ref "C70") (pin "1") (pinfunction "1_1") (pintype "passive"))
      (node (ref "C71") (pin "1") (pinfunction "1_1") (pintype "passive"))
      (node (ref "C72") (pin "1") (pinfunction "1_1") (pintype "passive"))
      (node (ref "C73") (pin "1") (pinfunction "1_1") (pintype "passive"))
      (node (ref "C74") (pin "1") (pinfunction "1_1") (pintype "passive"))
      (node (ref "C75") (pin "1") (pinfunction "1_1") (pintype "passive"))
      (node (ref "C76") (pin "1") (pinfunction "1_1") (pintype "passive"))
      (node (ref "C77") (pin "1") (pinfunction "1_1") (pintype "passive"))
      (node (ref "C78") (pin "1") (pinfunction "1_1") (pintype "passive"))
      (node (ref "C79") (pin "1") (pinfunction "1_1") (pintype "passive"))
      (node (ref "C80") (pin "1") (pinfunction "1_1") (pintype "passive"))
      (node (ref "C81") (pin "1") (pinfunction "1_1") (pintype "passive"))
      (node (ref "C82") (pin "1") (pinfunction "1_1") (pintype "passive"))
      (node (ref "C83") (pin "1") (pinfunction "1_1") (pintype "passive"))
      (node (ref "C84") (pin "1") (pinfunction "1_1") (pintype "passive"))
      (node (ref "C85") (pin "1") (pinfunction "1_1") (pintype "passive"))
      (node (ref "C86") (pin "1") (pinfunction "1_1") (pintype "passive"))
      (node (ref "C87") (pin "1") (pinfunction "1_1") (pintype "passive"))
      (node (ref "C88") (pin "1") (pinfunction "1_1") (pintype "passive"))
      (node (ref "C89") (pin "1") (pinfunction "1_1") (pintype "passive"))
      (node (ref "C90") (pin "1") (pinfunction "1_1") (pintype "passive"))
      (node (ref "C91") (pin "1") (pinfunction "1_1") (pintype "passive"))
      (node (ref "C92") (pin "1") (pinfunction "1_1") (pintype "passive"))
      (node (ref "C93") (pin "1") (pinfunction "1_1") (pintype "passive"))
      (node (ref "C94") (pin "1") (pinfunction "1_1") (pintype "passive"))
      (node (ref "C95") (pin "1") (pinfunction "1_1") (pintype "passive"))
      (node (ref "C96") (pin "1") (pinfunction "1_1") (pintype "passive"))
      (node (ref "C97") (pin "1") (pinfunction "1_1") (pintype "passive"))
      (node (ref "C98") (pin "1") (pinfunction "1_1") (pintype "passive"))
      (node (ref "C99") (pin "1") (pinfunction "1_1") (pintype "passive"))
      (node (ref "U6") (pin "A1") (pinfunction "GND_A1") (pintype "power_in"))
      (node (ref "U6") (pin "A22") (pinfunction "GND_A22") (pintype "power_in"))
      (node (ref "U6") (pin "AA2") (pinfunction "GND_AA2") (pintype "power_in"))
      (node (ref "U6") (pin "AA22") (pinfunction "GND_AA22") (pintype "power_in"))
      (node (ref "U6") (pin "AB1") (pinfunction "GND_AB1") (pintype "power_in"))
      (node (ref "U6") (pin "AB22") (pinfunction "GND_AB22") (pintype "power_in"))
      (node (ref "U6") (pin "AB6") (pinfunction "GND_AB6") (pintype "power_in"))
      (node (ref "U6") (pin "C11") (pinfunction "GND_C11") (pintype "power_in"))
      (node (ref "U6") (pin "C12") (pinfunction "GND_C12") (pintype "power_in"))
      (node (ref "U6") (pin "C14") (pinfunction "GND_C14") (pintype "power_in"))
      (node (ref "U6") (pin "C16") (pinfunction "GND_C16") (pintype "power_in"))
      (node (ref "U6") (pin "C18") (pinfunction "GND_C18") (pintype "power_in"))
      (node (ref "U6") (pin "C5") (pinfunction "GND_C5") (pintype "power_in"))
      (node (ref "U6") (pin "C9") (pinfunction "GND_C9") (pintype "power_in"))
      (node (ref "U6") (pin "D3") (pinfunction "GND_D3") (pintype "power_in"))
      (node (ref "U6") (pin "D7") (pinfunction "GND_D7") (pintype "power_in"))
      (node (ref "U6") (pin "D8") (pinfunction "GND_D8") (pintype "power_in"))
      (node (ref "U6") (pin "E18") (pinfunction "GNDA2_E18") (pintype "power_in"))
      (node (ref "U6") (pin "E20") (pinfunction "GND_E20") (pintype "power_in"))
      (node (ref "U6") (pin "F3") (pinfunction "GND_F3") (pintype "power_in"))
      (node (ref "U6") (pin "F5") (pinfunction "GNDA3_F5") (pintype "power_in"))
      (node (ref "U6") (pin "G2") (pinfunction "GND_G2") (pintype "power_in"))
      (node (ref "U6") (pin "G20") (pinfunction "GND_G20") (pintype "power_in"))
      (node (ref "U6") (pin "H3") (pinfunction "GND_H3") (pintype "power_in"))
      (node (ref "U6") (pin "H8") (pinfunction "GND_H8") (pintype "power_in"))
      (node (ref "U6") (pin "J19") (pinfunction "GND_J19") (pintype "power_in"))
      (node (ref "U6") (pin "J5") (pinfunction "GND_J5") (pintype "power_in"))
      (node (ref "U6") (pin "J9") (pinfunction "GND_J9") (pintype "power_in"))
      (node (ref "U6") (pin "K10") (pinfunction "GND_K10") (pintype "power_in"))
      (node (ref "U6") (pin "K11") (pinfunction "GND_K11") (pintype "power_in"))
      (node (ref "U6") (pin "K12") (pinfunction "GND_K12") (pintype "power_in"))
      (node (ref "U6") (pin "K13") (pinfunction "GND_K13") (pintype "power_in"))
      (node (ref "U6") (pin "K20") (pinfunction "MSEL3_K20") (pintype "input"))
      (node (ref "U6") (pin "K3") (pinfunction "GND_K3") (pintype "power_in"))
      (node (ref "U6") (pin "L10") (pinfunction "GND_L10") (pintype "power_in"))
      (node (ref "U6") (pin "L11") (pinfunction "GND_L11") (pintype "power_in"))
      (node (ref "U6") (pin "L12") (pinfunction "GND_L12") (pintype "power_in"))
      (node (ref "U6") (pin "L13") (pinfunction "GND_L13") (pintype "power_in"))
      (node (ref "U6") (pin "L17") (pinfunction "MSEL2_L17") (pintype "input"))
      (node (ref "U6") (pin "L18") (pinfunction "MSEL1_L18") (pintype "input"))
      (node (ref "U6") (pin "L20") (pinfunction "GND_L20") (pintype "power_in"))
      (node (ref "U6") (pin "L3") (pinfunction "nCE_L3") (pintype "input"))
      (node (ref "U6") (pin "M10") (pinfunction "GND_M10") (pintype "power_in"))
      (node (ref "U6") (pin "M11") (pinfunction "GND_M11") (pintype "power_in"))
      (node (ref "U6") (pin "M12") (pinfunction "GND_M12") (pintype "power_in"))
      (node (ref "U6") (pin "M13") (pinfunction "GND_M13") (pintype "power_in"))
      (node (ref "U6") (pin "M17") (pinfunction "MSEL0_M17") (pintype "input"))
      (node (ref "U6") (pin "N10") (pinfunction "GND_N10") (pintype "power_in"))
      (node (ref "U6") (pin "N11") (pinfunction "GND_N11") (pintype "power_in"))
      (node (ref "U6") (pin "N12") (pinfunction "GND_N12") (pintype "power_in"))
      (node (ref "U6") (pin "N13") (pinfunction "GND_N13") (pintype "power_in"))
      (node (ref "U6") (pin "N3") (pinfunction "GND_N3") (pintype "power_in"))
      (node (ref "U6") (pin "P19") (pinfunction "GND_P19") (pintype "power_in"))
      (node (ref "U6") (pin "R3") (pinfunction "GND_R3") (pintype "power_in"))
      (node (ref "U6") (pin "T20") (pinfunction "GND_T20") (pintype "power_in"))
      (node (ref "U6") (pin "U3") (pinfunction "GND_U3") (pintype "power_in"))
      (node (ref "U6") (pin "U5") (pinfunction "GNDA1_U5") (pintype "power_in"))
      (node (ref "U6") (pin "V18") (pinfunction "GNDA4_V18") (pintype "power_in"))
      (node (ref "U6") (pin "V20") (pinfunction "GND_V20") (pintype "power_in"))
      (node (ref "U6") (pin "W3") (pinfunction "GND_W3") (pintype "power_in"))
      (node (ref "U6") (pin "Y11") (pinfunction "GND_Y11") (pintype "power_in"))
      (node (ref "U6") (pin "Y12") (pinfunction "GND_Y12") (pintype "power_in"))
      (node (ref "U6") (pin "Y15") (pinfunction "GND_Y15") (pintype "power_in"))
      (node (ref "U6") (pin "Y16") (pinfunction "GND_Y16") (pintype "power_in"))
      (node (ref "U6") (pin "Y18") (pinfunction "GND_Y18") (pintype "power_in"))
      (node (ref "U6") (pin "Y20") (pinfunction "GND_Y20") (pintype "power_in"))
      (node (ref "U6") (pin "Y5") (pinfunction "GND_Y5") (pintype "power_in"))
      (node (ref "U6") (pin "Y9") (pinfunction "GND_Y9") (pintype "power_in"))
    )
  )
)
